# melzi.net
KiCad netlist of a schematic drawn in EAGLE
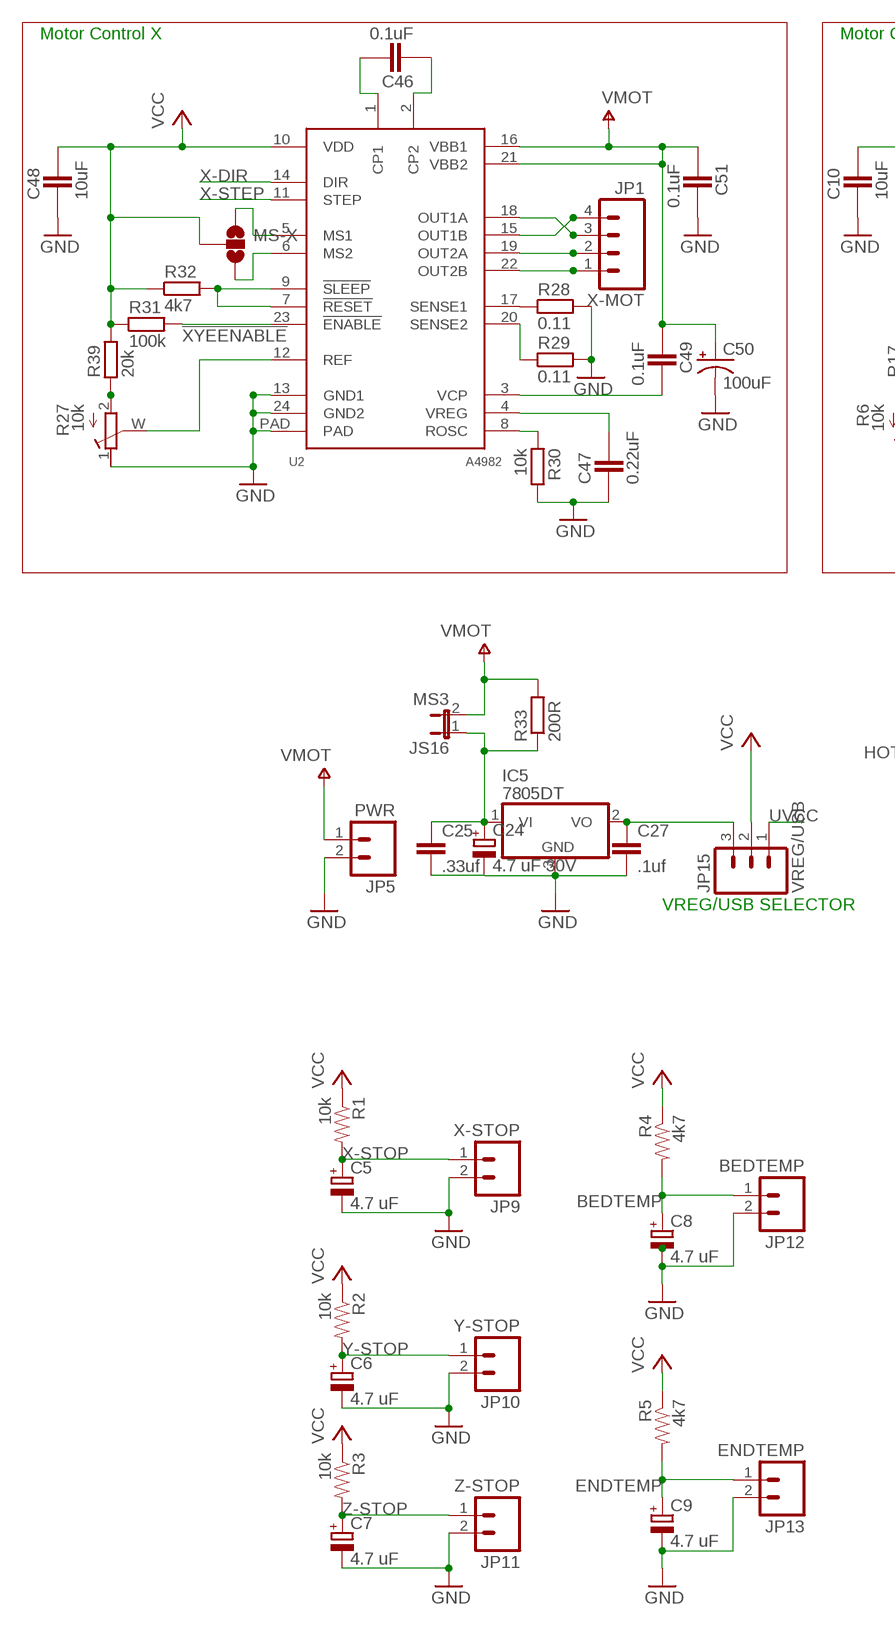
[diagram p0: schematic, sheet 1, part 1 of 2]
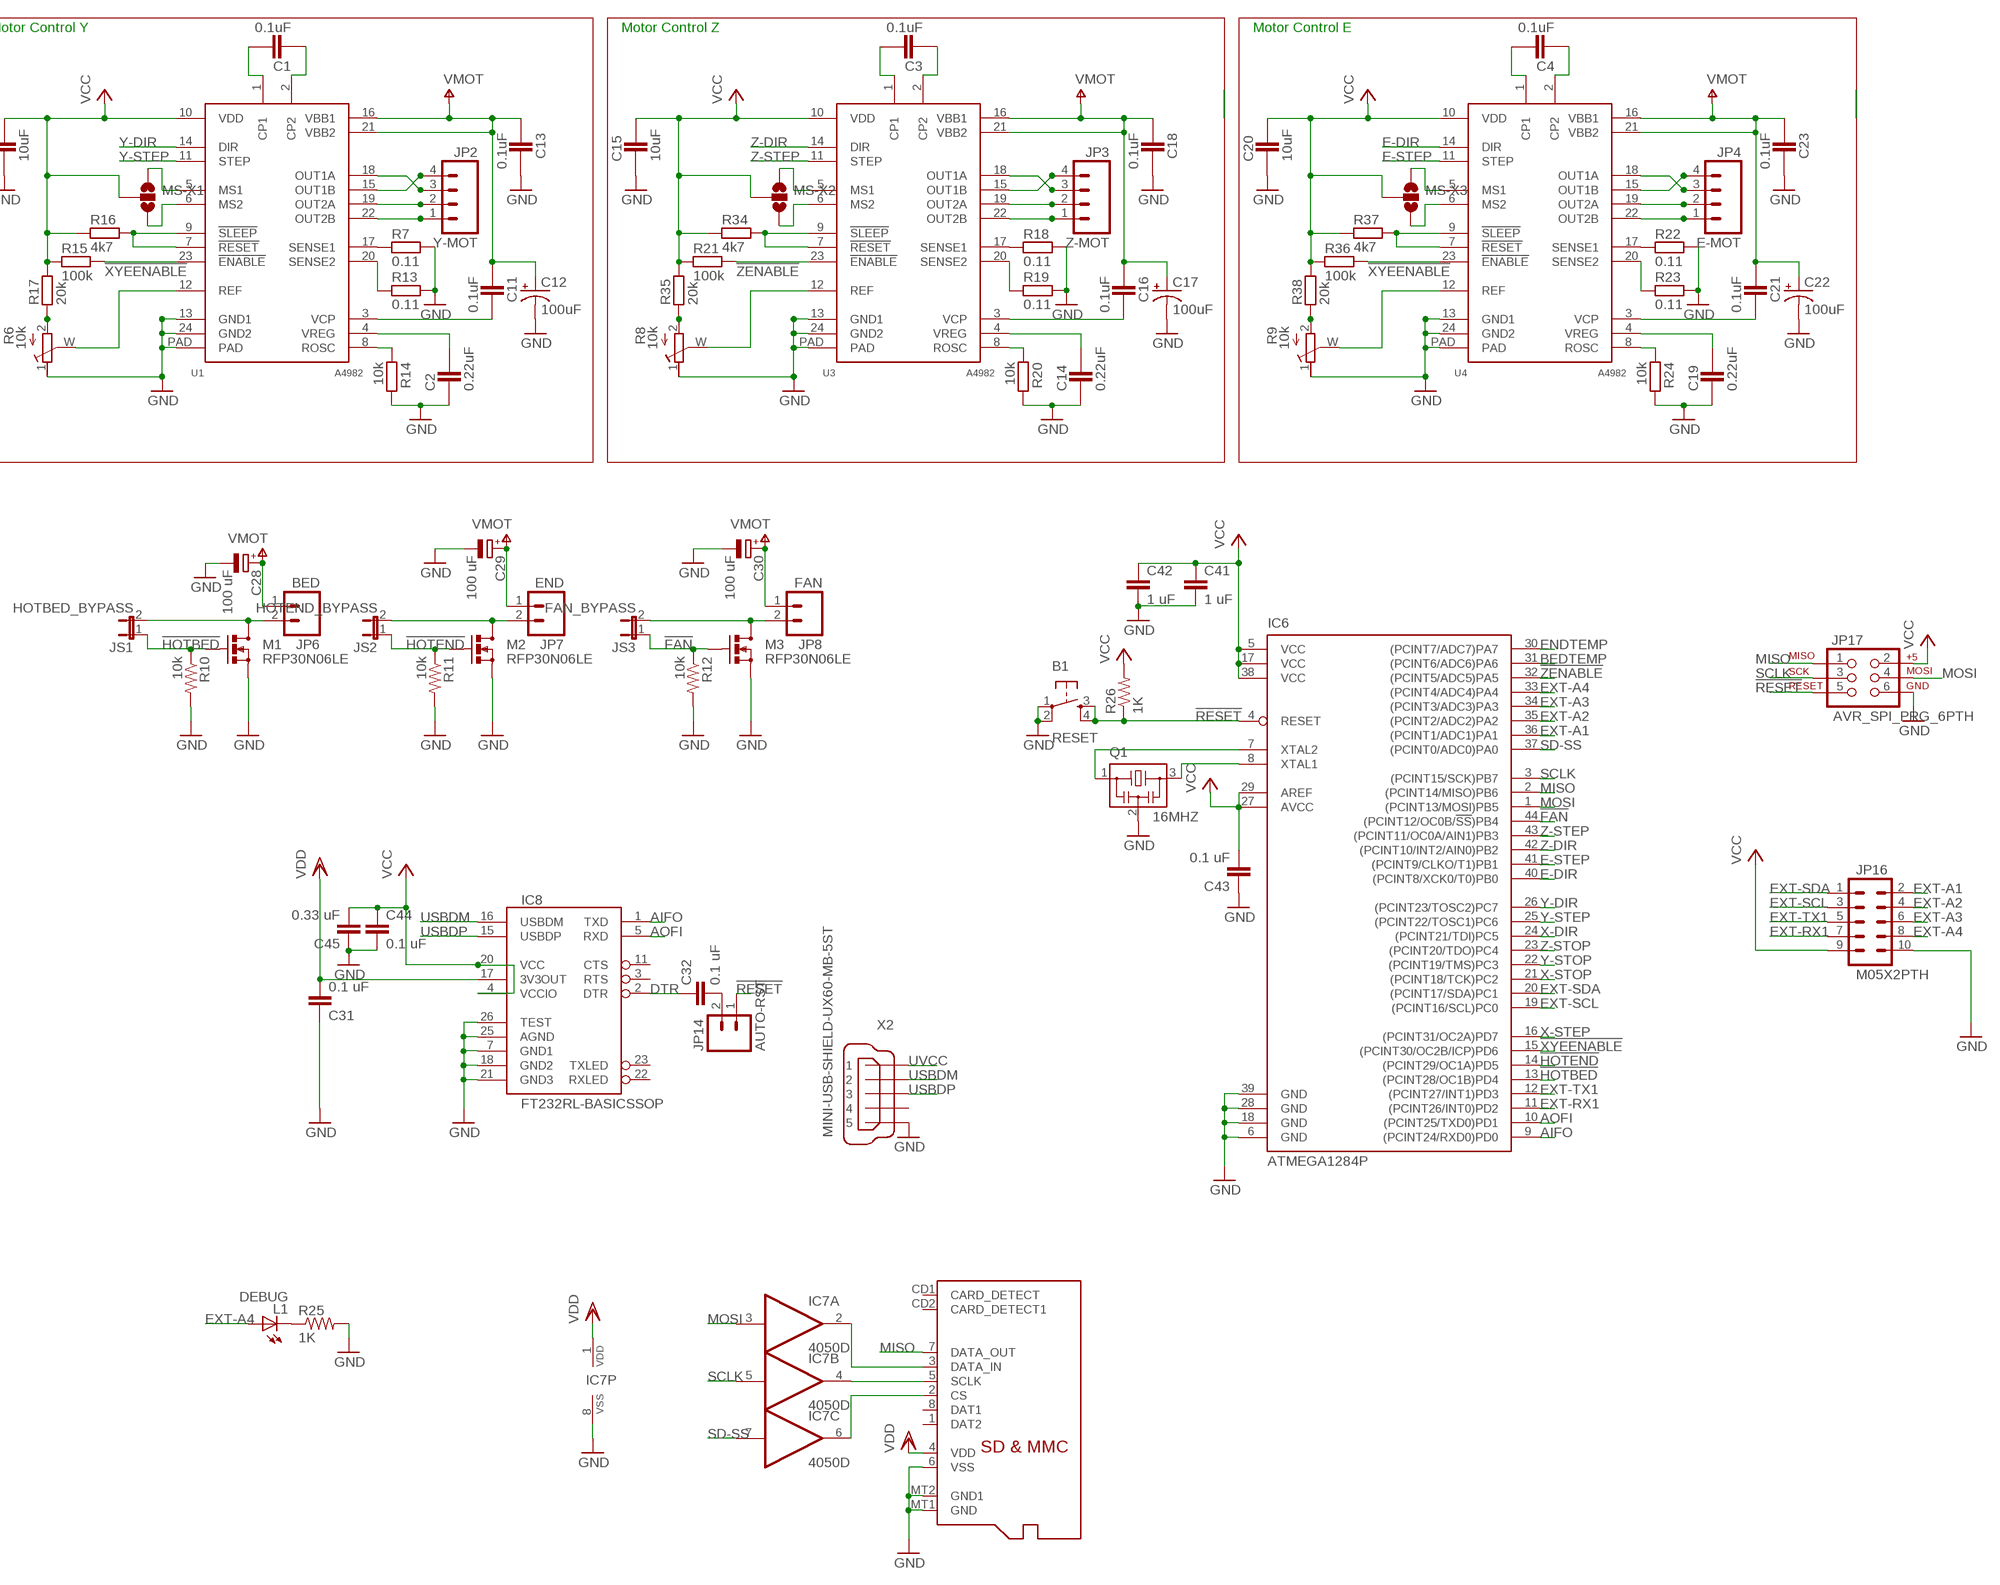
[diagram p1: schematic, sheet 1, part 2 of 2]

(export (version "E")
  (design (tool "Eeschema 10.0.6"))
  (components
    (comp (ref "B1")
      (value "RESET")
      (footprint "eagle-import:TACTILE_SWITCH_SMD")
      (libsource (lib "eagle-import") (part "TAC_SWITCHSMD"))
    )
    (comp (ref "C1")
      (value "0.1uF")
      (footprint "eagle-import:CAPC2012X145AN")
      (libsource (lib "eagle-import") (part "CAPACITOR_0805"))
    )
    (comp (ref "C2")
      (value "0.22uF")
      (footprint "eagle-import:CAPC2012X145AN")
      (libsource (lib "eagle-import") (part "CAPACITOR_0805"))
    )
    (comp (ref "C3")
      (value "0.1uF")
      (footprint "eagle-import:CAPC2012X145AN")
      (libsource (lib "eagle-import") (part "CAPACITOR_0805"))
    )
    (comp (ref "C4")
      (value "0.1uF")
      (footprint "eagle-import:CAPC2012X145AN")
      (libsource (lib "eagle-import") (part "CAPACITOR_0805"))
    )
    (comp (ref "C5")
      (value "4.7 uF")
      (footprint "eagle-import:SMC_C")
      (libsource (lib "eagle-import") (part "CPOL-EUSMCC"))
    )
    (comp (ref "C6")
      (value "4.7 uF")
      (footprint "eagle-import:SMC_C")
      (libsource (lib "eagle-import") (part "CPOL-EUSMCC"))
    )
    (comp (ref "C7")
      (value "4.7 uF")
      (footprint "eagle-import:SMC_C")
      (libsource (lib "eagle-import") (part "CPOL-EUSMCC"))
    )
    (comp (ref "C8")
      (value "4.7 uF")
      (footprint "eagle-import:SMC_C")
      (libsource (lib "eagle-import") (part "CPOL-EUSMCC"))
    )
    (comp (ref "C9")
      (value "4.7 uF")
      (footprint "eagle-import:SMC_C")
      (libsource (lib "eagle-import") (part "CPOL-EUSMCC"))
    )
    (comp (ref "C10")
      (value "10uF")
      (footprint "eagle-import:CAPC2012X145AN")
      (libsource (lib "eagle-import") (part "CAPACITOR_0805"))
    )
    (comp (ref "C11")
      (value "0.1uF")
      (footprint "eagle-import:CAPC2012X145AN")
      (libsource (lib "eagle-import") (part "CAPACITOR_0805"))
    )
    (comp (ref "C12")
      (value "100uF")
      (footprint "eagle-import:PANASONIC_D")
      (libsource (lib "eagle-import") (part "CPOL-USD"))
    )
    (comp (ref "C13")
      (value "0.1uF")
      (footprint "eagle-import:CAPC2012X145AN")
      (libsource (lib "eagle-import") (part "CAPACITOR_0805"))
    )
    (comp (ref "C14")
      (value "0.22uF")
      (footprint "eagle-import:CAPC2012X145AN")
      (libsource (lib "eagle-import") (part "CAPACITOR_0805"))
    )
    (comp (ref "C15")
      (value "10uF")
      (footprint "eagle-import:CAPC2012X145AN")
      (libsource (lib "eagle-import") (part "CAPACITOR_0805"))
    )
    (comp (ref "C16")
      (value "0.1uF")
      (footprint "eagle-import:CAPC2012X145AN")
      (libsource (lib "eagle-import") (part "CAPACITOR_0805"))
    )
    (comp (ref "C17")
      (value "100uF")
      (footprint "eagle-import:PANASONIC_D")
      (libsource (lib "eagle-import") (part "CPOL-USD"))
    )
    (comp (ref "C18")
      (value "0.1uF")
      (footprint "eagle-import:CAPC2012X145AN")
      (libsource (lib "eagle-import") (part "CAPACITOR_0805"))
    )
    (comp (ref "C19")
      (value "0.22uF")
      (footprint "eagle-import:CAPC2012X145AN")
      (libsource (lib "eagle-import") (part "CAPACITOR_0805"))
    )
    (comp (ref "C20")
      (value "10uF")
      (footprint "eagle-import:CAPC2012X145AN")
      (libsource (lib "eagle-import") (part "CAPACITOR_0805"))
    )
    (comp (ref "C21")
      (value "0.1uF")
      (footprint "eagle-import:CAPC2012X145AN")
      (libsource (lib "eagle-import") (part "CAPACITOR_0805"))
    )
    (comp (ref "C22")
      (value "100uF")
      (footprint "eagle-import:PANASONIC_D")
      (libsource (lib "eagle-import") (part "CPOL-USD"))
    )
    (comp (ref "C23")
      (value "0.1uF")
      (footprint "eagle-import:CAPC2012X145AN")
      (libsource (lib "eagle-import") (part "CAPACITOR_0805"))
    )
    (comp (ref "C24")
      (value "4.7 uF 30V")
      (footprint "eagle-import:SMC_C")
      (libsource (lib "eagle-import") (part "CPOL-EUSMCC"))
    )
    (comp (ref "C25")
      (value ".33uf")
      (footprint "eagle-import:0805")
      (libsource (lib "eagle-import") (part "CAP0805"))
    )
    (comp (ref "C27")
      (value ".1uf")
      (footprint "eagle-import:0805")
      (libsource (lib "eagle-import") (part "CAP0805"))
    )
    (comp (ref "C28")
      (value "100 uF")
      (footprint "eagle-import:UD-6,3X7,7_NICHICON")
      (libsource (lib "eagle-import") (part "CPOL-EUUD-6,3X7,7"))
    )
    (comp (ref "C29")
      (value "100 uF")
      (footprint "eagle-import:UD-6,3X7,7_NICHICON")
      (libsource (lib "eagle-import") (part "CPOL-EUUD-6,3X7,7"))
    )
    (comp (ref "C30")
      (value "100 uF")
      (footprint "eagle-import:UD-6,3X7,7_NICHICON")
      (libsource (lib "eagle-import") (part "CPOL-EUUD-6,3X7,7"))
    )
    (comp (ref "C31")
      (value "0.1 uF")
      (footprint "eagle-import:C1206")
      (libsource (lib "eagle-import") (part "C-EUC1206"))
    )
    (comp (ref "C32")
      (value "0.1 uF")
      (footprint "eagle-import:C1206")
      (libsource (lib "eagle-import") (part "C-EUC1206"))
    )
    (comp (ref "C41")
      (value "1 uF")
      (footprint "eagle-import:C1206")
      (libsource (lib "eagle-import") (part "C-EUC1206"))
    )
    (comp (ref "C42")
      (value "1 uF")
      (footprint "eagle-import:C1206")
      (libsource (lib "eagle-import") (part "C-EUC1206"))
    )
    (comp (ref "C43")
      (value "0.1 uF")
      (footprint "eagle-import:C1206")
      (libsource (lib "eagle-import") (part "C-EUC1206"))
    )
    (comp (ref "C44")
      (value "0.1 uF")
      (footprint "eagle-import:C1206")
      (libsource (lib "eagle-import") (part "C-EUC1206"))
    )
    (comp (ref "C45")
      (value "0.33 uF")
      (footprint "eagle-import:C1206")
      (libsource (lib "eagle-import") (part "C-EUC1206"))
    )
    (comp (ref "C46")
      (value "0.1uF")
      (footprint "eagle-import:CAPC2012X145AN")
      (libsource (lib "eagle-import") (part "CAPACITOR_0805"))
    )
    (comp (ref "C47")
      (value "0.22uF")
      (footprint "eagle-import:CAPC2012X145AN")
      (libsource (lib "eagle-import") (part "CAPACITOR_0805"))
    )
    (comp (ref "C48")
      (value "10uF")
      (footprint "eagle-import:CAPC2012X145AN")
      (libsource (lib "eagle-import") (part "CAPACITOR_0805"))
    )
    (comp (ref "C49")
      (value "0.1uF")
      (footprint "eagle-import:CAPC2012X145AN")
      (libsource (lib "eagle-import") (part "CAPACITOR_0805"))
    )
    (comp (ref "C50")
      (value "100uF")
      (footprint "eagle-import:PANASONIC_D")
      (libsource (lib "eagle-import") (part "CPOL-USD"))
    )
    (comp (ref "C51")
      (value "0.1uF")
      (footprint "eagle-import:CAPC2012X145AN")
      (libsource (lib "eagle-import") (part "CAPACITOR_0805"))
    )
    (comp (ref "IC5")
      (value "7805DT")
      (footprint "eagle-import:TO252")
      (libsource (lib "eagle-import") (part "78DT05"))
    )
    (comp (ref "IC6")
      (value "ATMEGA1284P")
      (footprint "eagle-import:TQFP44")
      (fields (field (name "MPN") "ATMEGA644PV-10AU"))
      (libsource (lib "eagle-import") (part "ATMEGA644A"))
    )
    (comp (ref "IC7")
      (value "4050D")
      (footprint "eagle-import:SO16")
      (libsource (lib "eagle-import") (part "4050D"))
    )
    (comp (ref "IC8")
      (value "FT232RL-BASICSSOP")
      (footprint "eagle-import:SSOP28DB")
      (libsource (lib "eagle-import") (part "FT232RL-BASICSSOP"))
    )
    (comp (ref "JP1")
      (value "X-MOT")
      (footprint "eagle-import:SCREWTERMINAL-3.5MM-4")
      (libsource (lib "eagle-import") (part "M04SCREW"))
    )
    (comp (ref "JP2")
      (value "Y-MOT")
      (footprint "eagle-import:SCREWTERMINAL-3.5MM-4")
      (libsource (lib "eagle-import") (part "M04SCREW"))
    )
    (comp (ref "JP3")
      (value "Z-MOT")
      (footprint "eagle-import:SCREWTERMINAL-3.5MM-4")
      (libsource (lib "eagle-import") (part "M04SCREW"))
    )
    (comp (ref "JP4")
      (value "E-MOT")
      (footprint "eagle-import:SCREWTERMINAL-3.5MM-4")
      (libsource (lib "eagle-import") (part "M04SCREW"))
    )
    (comp (ref "JP5")
      (value "PWR")
      (footprint "eagle-import:SCREWTERMINAL-5MM-2")
      (libsource (lib "eagle-import") (part "M025MM"))
    )
    (comp (ref "JP6")
      (value "BED")
      (footprint "eagle-import:SCREWTERMINAL-5MM-2")
      (libsource (lib "eagle-import") (part "M025MM"))
    )
    (comp (ref "JP7")
      (value "END")
      (footprint "eagle-import:SCREWTERMINAL-5MM-2")
      (libsource (lib "eagle-import") (part "M025MM"))
    )
    (comp (ref "JP8")
      (value "FAN")
      (footprint "eagle-import:SCREWTERMINAL-5MM-2")
      (libsource (lib "eagle-import") (part "M025MM"))
    )
    (comp (ref "JP9")
      (value "X-STOP")
      (footprint "eagle-import:SCREWTERMINAL-3.5MM-2")
      (libsource (lib "eagle-import") (part "M023.5MM"))
    )
    (comp (ref "JP10")
      (value "Y-STOP")
      (footprint "eagle-import:SCREWTERMINAL-3.5MM-2")
      (libsource (lib "eagle-import") (part "M023.5MM"))
    )
    (comp (ref "JP11")
      (value "Z-STOP")
      (footprint "eagle-import:SCREWTERMINAL-3.5MM-2")
      (libsource (lib "eagle-import") (part "M023.5MM"))
    )
    (comp (ref "JP12")
      (value "BEDTEMP")
      (footprint "eagle-import:SCREWTERMINAL-3.5MM-2")
      (libsource (lib "eagle-import") (part "M023.5MM"))
    )
    (comp (ref "JP13")
      (value "ENDTEMP")
      (footprint "eagle-import:SCREWTERMINAL-3.5MM-2")
      (libsource (lib "eagle-import") (part "M023.5MM"))
    )
    (comp (ref "JP14")
      (value "AUTO-RST")
      (footprint "eagle-import:1X02")
      (libsource (lib "eagle-import") (part "M02PTH"))
    )
    (comp (ref "JP15")
      (value "VREG/USB")
      (footprint "eagle-import:1X03")
      (libsource (lib "eagle-import") (part "M03PTH"))
    )
    (comp (ref "JP16")
      (value "M05X2PTH")
      (footprint "eagle-import:AVR_ICSP")
      (libsource (lib "eagle-import") (part "M05X2PTH"))
    )
    (comp (ref "JP17")
      (value "AVR_SPI_PRG_6PTH")
      (footprint "eagle-import:2X3")
      (libsource (lib "eagle-import") (part "AVR_SPI_PRG_6PTH"))
    )
    (comp (ref "JS1")
      (value "HOTBED_BYPASS")
      (footprint "eagle-import:SJ_2S-NO")
      (libsource (lib "eagle-import") (part "JUMPER-2SMD-NO"))
    )
    (comp (ref "JS2")
      (value "HOTEND_BYPASS")
      (footprint "eagle-import:SJ_2S-NO")
      (libsource (lib "eagle-import") (part "JUMPER-2SMD-NO"))
    )
    (comp (ref "JS3")
      (value "FAN_BYPASS")
      (footprint "eagle-import:SJ_2S-NO")
      (libsource (lib "eagle-import") (part "JUMPER-2SMD-NO"))
    )
    (comp (ref "JS16")
      (value "MS3")
      (footprint "eagle-import:SJ_2S")
      (libsource (lib "eagle-import") (part "JUMPER-2SMD-NC"))
    )
    (comp (ref "L1")
      (value "DEBUG")
      (footprint "eagle-import:LED-1206")
      (libsource (lib "eagle-import") (part "LED1206"))
    )
    (comp (ref "M1")
      (value "RFP30N06LE")
      (footprint "eagle-import:DPAK")
      (libsource (lib "eagle-import") (part "MOSFET-NCHANNELFDD8580"))
    )
    (comp (ref "M2")
      (value "RFP30N06LE")
      (footprint "eagle-import:DPAK")
      (libsource (lib "eagle-import") (part "MOSFET-NCHANNELFDD8580"))
    )
    (comp (ref "M3")
      (value "RFP30N06LE")
      (footprint "eagle-import:DPAK")
      (libsource (lib "eagle-import") (part "MOSFET-NCHANNELFDD8580"))
    )
    (comp (ref "MS-X")
      (value "SOLDERJUMPER_2WAYCONNECTED")
      (footprint "eagle-import:SJ_3_CONNECTED")
      (libsource (lib "eagle-import") (part "SOLDERJUMPER_2WAYCONNECTED"))
    )
    (comp (ref "MS-X1")
      (value "SOLDERJUMPER_2WAYCONNECTED")
      (footprint "eagle-import:SJ_3_CONNECTED")
      (libsource (lib "eagle-import") (part "SOLDERJUMPER_2WAYCONNECTED"))
    )
    (comp (ref "MS-X2")
      (value "SOLDERJUMPER_2WAYCONNECTED")
      (footprint "eagle-import:SJ_3_CONNECTED")
      (libsource (lib "eagle-import") (part "SOLDERJUMPER_2WAYCONNECTED"))
    )
    (comp (ref "MS-X3")
      (value "SOLDERJUMPER_2WAYCONNECTED")
      (footprint "eagle-import:SJ_3_CONNECTED")
      (libsource (lib "eagle-import") (part "SOLDERJUMPER_2WAYCONNECTED"))
    )
    (comp (ref "Q1")
      (value "16MHZ")
      (footprint "eagle-import:CSTCR6M")
      (fields (field (name "MPN") "CSTCR6M00G53-R0"))
      (libsource (lib "eagle-import") (part "CSTCR6M00G53Z"))
    )
    (comp (ref "R1")
      (value "10k")
      (footprint "eagle-import:1206")
      (libsource (lib "eagle-import") (part "RESISTOR1206"))
    )
    (comp (ref "R2")
      (value "10k")
      (footprint "eagle-import:1206")
      (libsource (lib "eagle-import") (part "RESISTOR1206"))
    )
    (comp (ref "R3")
      (value "10k")
      (footprint "eagle-import:1206")
      (libsource (lib "eagle-import") (part "RESISTOR1206"))
    )
    (comp (ref "R4")
      (value "4k7")
      (footprint "eagle-import:1206")
      (libsource (lib "eagle-import") (part "RESISTOR1206"))
    )
    (comp (ref "R5")
      (value "4k7")
      (footprint "eagle-import:1206")
      (libsource (lib "eagle-import") (part "RESISTOR1206"))
    )
    (comp (ref "R6")
      (value "10k")
      (footprint "eagle-import:RTRIM-ST4ETB")
      (libsource (lib "eagle-import") (part "RTRIM-ST-4EA"))
    )
    (comp (ref "R7")
      (value "0.11")
      (footprint "eagle-import:RESC2012X70N")
      (libsource (lib "eagle-import") (part "RESISTOR_0805"))
    )
    (comp (ref "R8")
      (value "10k")
      (footprint "eagle-import:RTRIM-ST4ETB")
      (libsource (lib "eagle-import") (part "RTRIM-ST-4EA"))
    )
    (comp (ref "R9")
      (value "10k")
      (footprint "eagle-import:RTRIM-ST4ETB")
      (libsource (lib "eagle-import") (part "RTRIM-ST-4EA"))
    )
    (comp (ref "R10")
      (value "10k")
      (footprint "eagle-import:1206")
      (libsource (lib "eagle-import") (part "RESISTOR1206"))
    )
    (comp (ref "R11")
      (value "10k")
      (footprint "eagle-import:1206")
      (libsource (lib "eagle-import") (part "RESISTOR1206"))
    )
    (comp (ref "R12")
      (value "10k")
      (footprint "eagle-import:1206")
      (libsource (lib "eagle-import") (part "RESISTOR1206"))
    )
    (comp (ref "R13")
      (value "0.11")
      (footprint "eagle-import:RESC2012X70N")
      (libsource (lib "eagle-import") (part "RESISTOR_0805"))
    )
    (comp (ref "R14")
      (value "10k")
      (footprint "eagle-import:RESC2012X70N")
      (libsource (lib "eagle-import") (part "RESISTOR_0805"))
    )
    (comp (ref "R15")
      (value "100k")
      (footprint "eagle-import:RESC2012X70N")
      (libsource (lib "eagle-import") (part "RESISTOR_0805"))
    )
    (comp (ref "R16")
      (value "4k7")
      (footprint "eagle-import:RESC2012X70N")
      (libsource (lib "eagle-import") (part "RESISTOR_0805"))
    )
    (comp (ref "R17")
      (value "20k")
      (footprint "eagle-import:RESC2012X70N")
      (libsource (lib "eagle-import") (part "RESISTOR_0805"))
    )
    (comp (ref "R18")
      (value "0.11")
      (footprint "eagle-import:RESC2012X70N")
      (libsource (lib "eagle-import") (part "RESISTOR_0805"))
    )
    (comp (ref "R19")
      (value "0.11")
      (footprint "eagle-import:RESC2012X70N")
      (libsource (lib "eagle-import") (part "RESISTOR_0805"))
    )
    (comp (ref "R20")
      (value "10k")
      (footprint "eagle-import:RESC2012X70N")
      (libsource (lib "eagle-import") (part "RESISTOR_0805"))
    )
    (comp (ref "R21")
      (value "100k")
      (footprint "eagle-import:RESC2012X70N")
      (libsource (lib "eagle-import") (part "RESISTOR_0805"))
    )
    (comp (ref "R22")
      (value "0.11")
      (footprint "eagle-import:RESC2012X70N")
      (libsource (lib "eagle-import") (part "RESISTOR_0805"))
    )
    (comp (ref "R23")
      (value "0.11")
      (footprint "eagle-import:RESC2012X70N")
      (libsource (lib "eagle-import") (part "RESISTOR_0805"))
    )
    (comp (ref "R24")
      (value "10k")
      (footprint "eagle-import:RESC2012X70N")
      (libsource (lib "eagle-import") (part "RESISTOR_0805"))
    )
    (comp (ref "R25")
      (value "1K")
      (footprint "eagle-import:1206")
      (libsource (lib "eagle-import") (part "RESISTOR1206"))
    )
    (comp (ref "R26")
      (value "1K")
      (footprint "eagle-import:1206")
      (libsource (lib "eagle-import") (part "RESISTOR1206"))
    )
    (comp (ref "R27")
      (value "10k")
      (footprint "eagle-import:RTRIM-ST4ETB")
      (libsource (lib "eagle-import") (part "RTRIM-ST-4EA"))
    )
    (comp (ref "R28")
      (value "0.11")
      (footprint "eagle-import:RESC2012X70N")
      (libsource (lib "eagle-import") (part "RESISTOR_0805"))
    )
    (comp (ref "R29")
      (value "0.11")
      (footprint "eagle-import:RESC2012X70N")
      (libsource (lib "eagle-import") (part "RESISTOR_0805"))
    )
    (comp (ref "R30")
      (value "10k")
      (footprint "eagle-import:RESC2012X70N")
      (libsource (lib "eagle-import") (part "RESISTOR_0805"))
    )
    (comp (ref "R31")
      (value "100k")
      (footprint "eagle-import:RESC2012X70N")
      (libsource (lib "eagle-import") (part "RESISTOR_0805"))
    )
    (comp (ref "R32")
      (value "4k7")
      (footprint "eagle-import:RESC2012X70N")
      (libsource (lib "eagle-import") (part "RESISTOR_0805"))
    )
    (comp (ref "R33")
      (value "200R")
      (footprint "eagle-import:0309V")
      (libsource (lib "eagle-import") (part "R-EU_0309/V"))
    )
    (comp (ref "R34")
      (value "4k7")
      (footprint "eagle-import:RESC2012X70N")
      (libsource (lib "eagle-import") (part "RESISTOR_0805"))
    )
    (comp (ref "R35")
      (value "20k")
      (footprint "eagle-import:RESC2012X70N")
      (libsource (lib "eagle-import") (part "RESISTOR_0805"))
    )
    (comp (ref "R36")
      (value "100k")
      (footprint "eagle-import:RESC2012X70N")
      (libsource (lib "eagle-import") (part "RESISTOR_0805"))
    )
    (comp (ref "R37")
      (value "4k7")
      (footprint "eagle-import:RESC2012X70N")
      (libsource (lib "eagle-import") (part "RESISTOR_0805"))
    )
    (comp (ref "R38")
      (value "20k")
      (footprint "eagle-import:RESC2012X70N")
      (libsource (lib "eagle-import") (part "RESISTOR_0805"))
    )
    (comp (ref "R39")
      (value "20k")
      (footprint "eagle-import:RESC2012X70N")
      (libsource (lib "eagle-import") (part "RESISTOR_0805"))
    )
    (comp (ref "U1")
      (value "A4982")
      (footprint "eagle-import:TSSOP-24")
      (libsource (lib "eagle-import") (part "A4982"))
    )
    (comp (ref "U2")
      (value "A4982")
      (footprint "eagle-import:TSSOP-24")
      (libsource (lib "eagle-import") (part "A4982"))
    )
    (comp (ref "U3")
      (value "A4982")
      (footprint "eagle-import:TSSOP-24")
      (libsource (lib "eagle-import") (part "A4982"))
    )
    (comp (ref "U4")
      (value "A4982")
      (footprint "eagle-import:TSSOP-24")
      (libsource (lib "eagle-import") (part "A4982"))
    )
    (comp (ref "X1")
      (value "MICROSD")
      (footprint "eagle-import:MICROSD")
      (libsource (lib "eagle-import") (part "MICROSD"))
    )
    (comp (ref "X2")
      (value "MINI-USB-SHIELD-UX60-MB-5ST")
      (footprint "eagle-import:UX60-MB-5ST")
      (libsource (lib "eagle-import") (part "MINI-USB-SHIELD-UX60-MB-5ST"))
    )
  )
  (nets
    (net (code "1") (name "/AIFO") (class "Default")
      (node (ref "IC6") (pin "9") (pinfunction "(PCINT24/RXD0)PD0_9") (pintype "bidirectional"))
      (node (ref "IC8") (pin "1") (pinfunction "TXD_1") (pintype "output"))
    )
    (net (code "2") (name "/AOFI") (class "Default")
      (node (ref "IC6") (pin "10") (pinfunction "(PCINT25/TXD0)PD1_10") (pintype "bidirectional"))
      (node (ref "IC8") (pin "5") (pinfunction "RXD_5") (pintype "input"))
    )
    (net (code "3") (name "/BEDTEMP") (class "Default")
      (node (ref "C8") (pin "+") (pinfunction "+_+") (pintype "passive"))
      (node (ref "IC6") (pin "31") (pinfunction "(PCINT6/ADC6)PA6_31") (pintype "bidirectional"))
      (node (ref "JP12") (pin "1") (pinfunction "1_1") (pintype "passive"))
      (node (ref "R4") (pin "2") (pinfunction "2_2") (pintype "passive"))
    )
    (net (code "4") (name "/DTR") (class "Default")
      (node (ref "C32") (pin "1") (pinfunction "1_1") (pintype "passive"))
      (node (ref "IC8") (pin "2") (pinfunction "DTR_2") (pintype "bidirectional"))
    )
    (net (code "5") (name "/E-DIR") (class "Default")
      (node (ref "IC6") (pin "40") (pinfunction "(PCINT8/XCK0/T0)PB0_40") (pintype "bidirectional"))
      (node (ref "U4") (pin "14") (pinfunction "DIR_14") (pintype "input"))
    )
    (net (code "6") (name "/E-STEP") (class "Default")
      (node (ref "IC6") (pin "41") (pinfunction "(PCINT9/CLKO/T1)PB1_41") (pintype "bidirectional"))
      (node (ref "U4") (pin "11") (pinfunction "STEP_11") (pintype "input"))
    )
    (net (code "7") (name "/ENDTEMP") (class "Default")
      (node (ref "C9") (pin "+") (pinfunction "+_+") (pintype "passive"))
      (node (ref "IC6") (pin "30") (pinfunction "(PCINT7/ADC7)PA7_30") (pintype "bidirectional"))
      (node (ref "JP13") (pin "1") (pinfunction "1_1") (pintype "passive"))
      (node (ref "R5") (pin "2") (pinfunction "2_2") (pintype "passive"))
    )
    (net (code "8") (name "/EXT-A1") (class "Default")
      (node (ref "IC6") (pin "36") (pinfunction "(PCINT1/ADC1)PA1_36") (pintype "bidirectional"))
      (node (ref "JP16") (pin "2") (pinfunction "2_2") (pintype "passive"))
    )
    (net (code "9") (name "/EXT-A2") (class "Default")
      (node (ref "IC6") (pin "35") (pinfunction "(PCINT2/ADC2)PA2_35") (pintype "bidirectional"))
      (node (ref "JP16") (pin "4") (pinfunction "4_4") (pintype "passive"))
    )
    (net (code "10") (name "/EXT-A3") (class "Default")
      (node (ref "IC6") (pin "34") (pinfunction "(PCINT3/ADC3)PA3_34") (pintype "bidirectional"))
      (node (ref "JP16") (pin "6") (pinfunction "6_6") (pintype "passive"))
    )
    (net (code "11") (name "/EXT-A4") (class "Default")
      (node (ref "IC6") (pin "33") (pinfunction "(PCINT4/ADC4)PA4_33") (pintype "bidirectional"))
      (node (ref "JP16") (pin "8") (pinfunction "8_8") (pintype "passive"))
      (node (ref "L1") (pin "A") (pinfunction "A_A") (pintype "passive"))
    )
    (net (code "12") (name "/EXT-RX1") (class "Default")
      (node (ref "IC6") (pin "11") (pinfunction "(PCINT26/INT0)PD2_11") (pintype "bidirectional"))
      (node (ref "JP16") (pin "7") (pinfunction "7_7") (pintype "passive"))
    )
    (net (code "13") (name "/EXT-SCL") (class "Default")
      (node (ref "IC6") (pin "19") (pinfunction "(PCINT16/SCL)PC0_19") (pintype "output"))
      (node (ref "JP16") (pin "3") (pinfunction "3_3") (pintype "passive"))
    )
    (net (code "14") (name "/EXT-SDA") (class "Default")
      (node (ref "IC6") (pin "20") (pinfunction "(PCINT17/SDA)PC1_20") (pintype "output"))
      (node (ref "JP16") (pin "1") (pinfunction "1_1") (pintype "passive"))
    )
    (net (code "15") (name "/EXT-TX1") (class "Default")
      (node (ref "IC6") (pin "12") (pinfunction "(PCINT27/INT1)PD3_12") (pintype "bidirectional"))
      (node (ref "JP16") (pin "5") (pinfunction "5_5") (pintype "passive"))
    )
    (net (code "16") (name "/MISO") (class "Default")
      (node (ref "IC6") (pin "2") (pinfunction "(PCINT14/MISO)PB6_2") (pintype "bidirectional"))
      (node (ref "JP17") (pin "1") (pinfunction "1_1") (pintype "passive"))
      (node (ref "X1") (pin "7") (pinfunction "DATA_OUT_7") (pintype "output"))
    )
    (net (code "17") (name "/MOSI") (class "Default")
      (node (ref "IC6") (pin "1") (pinfunction "(PCINT13/MOSI)PB5_1") (pintype "bidirectional"))
      (node (ref "IC7") (pin "3") (pinfunction "I_3") (pintype "input"))
      (node (ref "JP17") (pin "4") (pinfunction "4_4") (pintype "passive"))
    )
    (net (code "18") (name "/SCLK") (class "Default")
      (node (ref "IC6") (pin "3") (pinfunction "(PCINT15/SCK)PB7_3") (pintype "bidirectional"))
      (node (ref "IC7") (pin "5") (pinfunction "I_5") (pintype "input"))
      (node (ref "JP17") (pin "3") (pinfunction "3_3") (pintype "passive"))
    )
    (net (code "19") (name "/SD-SS") (class "Default")
      (node (ref "IC6") (pin "37") (pinfunction "(PCINT0/ADC0)PA0_37") (pintype "bidirectional"))
      (node (ref "IC7") (pin "7") (pinfunction "I_7") (pintype "input"))
    )
    (net (code "20") (name "/USBDM") (class "Default")
      (node (ref "IC8") (pin "16") (pinfunction "USBDM_16") (pintype "bidirectional"))
      (node (ref "X2") (pin "2") (pinfunction "2_2") (pintype "input"))
    )
    (net (code "21") (name "/USBDP") (class "Default")
      (node (ref "IC8") (pin "15") (pinfunction "USBDP_15") (pintype "bidirectional"))
      (node (ref "X2") (pin "3") (pinfunction "3_3") (pintype "input"))
    )
    (net (code "22") (name "/UVCC") (class "Default")
      (node (ref "JP15") (pin "1") (pinfunction "1_1") (pintype "passive"))
      (node (ref "X2") (pin "1") (pinfunction "1_1") (pintype "input"))
    )
    (net (code "23") (name "/X-DIR") (class "Default")
      (node (ref "IC6") (pin "24") (pinfunction "(PCINT21/TDI)PC5_24") (pintype "output"))
      (node (ref "U2") (pin "14") (pinfunction "DIR_14") (pintype "input"))
    )
    (net (code "24") (name "/X-STEP") (class "Default")
      (node (ref "IC6") (pin "16") (pinfunction "(PCINT31/OC2A)PD7_16") (pintype "bidirectional"))
      (node (ref "U2") (pin "11") (pinfunction "STEP_11") (pintype "input"))
    )
    (net (code "25") (name "/X-STOP") (class "Default")
      (node (ref "C5") (pin "+") (pinfunction "+_+") (pintype "passive"))
      (node (ref "IC6") (pin "21") (pinfunction "(PCINT18/TCK)PC2_21") (pintype "output"))
      (node (ref "JP9") (pin "1") (pinfunction "1_1") (pintype "passive"))
      (node (ref "R1") (pin "2") (pinfunction "2_2") (pintype "passive"))
    )
    (net (code "26") (name "/Y-DIR") (class "Default")
      (node (ref "IC6") (pin "26") (pinfunction "(PCINT23/TOSC2)PC7_26") (pintype "output"))
      (node (ref "U1") (pin "14") (pinfunction "DIR_14") (pintype "input"))
    )
    (net (code "27") (name "/Y-STEP") (class "Default")
      (node (ref "IC6") (pin "25") (pinfunction "(PCINT22/TOSC1)PC6_25") (pintype "output"))
      (node (ref "U1") (pin "11") (pinfunction "STEP_11") (pintype "input"))
    )
    (net (code "28") (name "/Y-STOP") (class "Default")
      (node (ref "C6") (pin "+") (pinfunction "+_+") (pintype "passive"))
      (node (ref "IC6") (pin "22") (pinfunction "(PCINT19/TMS)PC3_22") (pintype "output"))
      (node (ref "JP10") (pin "1") (pinfunction "1_1") (pintype "passive"))
      (node (ref "R2") (pin "2") (pinfunction "2_2") (pintype "passive"))
    )
    (net (code "29") (name "/Z-DIR") (class "Default")
      (node (ref "IC6") (pin "42") (pinfunction "(PCINT10/INT2/AIN0)PB2_42") (pintype "bidirectional"))
      (node (ref "U3") (pin "14") (pinfunction "DIR_14") (pintype "input"))
    )
    (net (code "30") (name "/Z-STEP") (class "Default")
      (node (ref "IC6") (pin "43") (pinfunction "(PCINT11/OC0A/AIN1)PB3_43") (pintype "bidirectional"))
      (node (ref "U3") (pin "11") (pinfunction "STEP_11") (pintype "input"))
    )
    (net (code "31") (name "/Z-STOP") (class "Default")
      (node (ref "C7") (pin "+") (pinfunction "+_+") (pintype "passive"))
      (node (ref "IC6") (pin "23") (pinfunction "(PCINT20/TDO)PC4_23") (pintype "output"))
      (node (ref "JP11") (pin "1") (pinfunction "1_1") (pintype "passive"))
      (node (ref "R3") (pin "2") (pinfunction "2_2") (pintype "passive"))
    )
    (net (code "32") (name "/~{FAN}") (class "Default")
      (node (ref "IC6") (pin "44") (pinfunction "(PCINT12/OC0B/~{SS})PB4_44") (pintype "bidirectional"))
      (node (ref "JS3") (pin "1") (pinfunction "1_1") (pintype "passive"))
      (node (ref "M3") (pin "1") (pinfunction "G_1") (pintype "passive"))
      (node (ref "R12") (pin "1") (pinfunction "1_1") (pintype "passive"))
    )
    (net (code "33") (name "/~{HOTBED}") (class "Default")
      (node (ref "IC6") (pin "13") (pinfunction "(PCINT28/OC1B)PD4_13") (pintype "bidirectional"))
      (node (ref "JS1") (pin "1") (pinfunction "1_1") (pintype "passive"))
      (node (ref "M1") (pin "1") (pinfunction "G_1") (pintype "passive"))
      (node (ref "R10") (pin "1") (pinfunction "1_1") (pintype "passive"))
    )
    (net (code "34") (name "/~{HOTEND}") (class "Default")
      (node (ref "IC6") (pin "14") (pinfunction "(PCINT29/OC1A)PD5_14") (pintype "bidirectional"))
      (node (ref "JS2") (pin "1") (pinfunction "1_1") (pintype "passive"))
      (node (ref "M2") (pin "1") (pinfunction "G_1") (pintype "passive"))
      (node (ref "R11") (pin "1") (pinfunction "1_1") (pintype "passive"))
    )
    (net (code "35") (name "/~{RESET}") (class "Default")
      (node (ref "B1") (pin "3") (pinfunction "3_3") (pintype "passive"))
      (node (ref "B1") (pin "4") (pinfunction "4_4") (pintype "passive"))
      (node (ref "IC6") (pin "4") (pinfunction "RESET_4") (pintype "input"))
      (node (ref "JP14") (pin "1") (pinfunction "1_1") (pintype "passive"))
      (node (ref "JP17") (pin "5") (pinfunction "5_5") (pintype "passive"))
      (node (ref "R26") (pin "1") (pinfunction "1_1") (pintype "passive"))
    )
    (net (code "36") (name "/~{XYEENABLE}") (class "Default")
      (node (ref "IC6") (pin "15") (pinfunction "(PCINT30/OC2B/ICP)PD6_15") (pintype "bidirectional"))
      (node (ref "R15") (pin "2") (pinfunction "2_2") (pintype "passive"))
      (node (ref "R31") (pin "2") (pinfunction "2_2") (pintype "passive"))
      (node (ref "R36") (pin "2") (pinfunction "2_2") (pintype "passive"))
      (node (ref "U1") (pin "23") (pinfunction "~{ENABLE}_23") (pintype "input"))
      (node (ref "U2") (pin "23") (pinfunction "~{ENABLE}_23") (pintype "input"))
      (node (ref "U4") (pin "23") (pinfunction "~{ENABLE}_23") (pintype "input"))
    )
    (net (code "37") (name "/~{ZENABLE}") (class "Default")
      (node (ref "IC6") (pin "32") (pinfunction "(PCINT5/ADC5)PA5_32") (pintype "bidirectional"))
      (node (ref "R21") (pin "2") (pinfunction "2_2") (pintype "passive"))
      (node (ref "U3") (pin "23") (pinfunction "~{ENABLE}_23") (pintype "input"))
    )
    (net (code "38") (name "GND") (class "Default")
      (node (ref "B1") (pin "1") (pinfunction "1_1") (pintype "passive"))
      (node (ref "B1") (pin "2") (pinfunction "2_2") (pintype "passive"))
      (node (ref "C10") (pin "1") (pinfunction "1_1") (pintype "passive"))
      (node (ref "C12") (pin "-") (pinfunction "-_-") (pintype "passive"))
      (node (ref "C13") (pin "2") (pinfunction "2_2") (pintype "passive"))
      (node (ref "C14") (pin "1") (pinfunction "1_1") (pintype "passive"))
      (node (ref "C15") (pin "1") (pinfunction "1_1") (pintype "passive"))
      (node (ref "C17") (pin "-") (pinfunction "-_-") (pintype "passive"))
      (node (ref "C18") (pin "2") (pinfunction "2_2") (pintype "passive"))
      (node (ref "C19") (pin "1") (pinfunction "1_1") (pintype "passive"))
      (node (ref "C2") (pin "1") (pinfunction "1_1") (pintype "passive"))
      (node (ref "C20") (pin "1") (pinfunction "1_1") (pintype "passive"))
      (node (ref "C22") (pin "-") (pinfunction "-_-") (pintype "passive"))
      (node (ref "C23") (pin "2") (pinfunction "2_2") (pintype "passive"))
      (node (ref "C24") (pin "-") (pinfunction "-_-") (pintype "passive"))
      (node (ref "C25") (pin "2") (pinfunction "2_2") (pintype "passive"))
      (node (ref "C27") (pin "2") (pinfunction "2_2") (pintype "passive"))
      (node (ref "C28") (pin "-") (pinfunction "-_-") (pintype "passive"))
      (node (ref "C29") (pin "-") (pinfunction "-_-") (pintype "passive"))
      (node (ref "C30") (pin "-") (pinfunction "-_-") (pintype "passive"))
      (node (ref "C31") (pin "1") (pinfunction "1_1") (pintype "passive"))
      (node (ref "C41") (pin "2") (pinfunction "2_2") (pintype "passive"))
      (node (ref "C42") (pin "2") (pinfunction "2_2") (pintype "passive"))
      (node (ref "C43") (pin "1") (pinfunction "1_1") (pintype "passive"))
      (node (ref "C44") (pin "2") (pinfunction "2_2") (pintype "passive"))
      (node (ref "C45") (pin "1") (pinfunction "1_1") (pintype "passive"))
      (node (ref "C47") (pin "1") (pinfunction "1_1") (pintype "passive"))
      (node (ref "C48") (pin "1") (pinfunction "1_1") (pintype "passive"))
      (node (ref "C5") (pin "-") (pinfunction "-_-") (pintype "passive"))
      (node (ref "C50") (pin "-") (pinfunction "-_-") (pintype "passive"))
      (node (ref "C51") (pin "2") (pinfunction "2_2") (pintype "passive"))
      (node (ref "C6") (pin "-") (pinfunction "-_-") (pintype "passive"))
      (node (ref "C7") (pin "-") (pinfunction "-_-") (pintype "passive"))
      (node (ref "C8") (pin "-") (pinfunction "-_-") (pintype "passive"))
      (node (ref "C9") (pin "-") (pinfunction "-_-") (pintype "passive"))
      (node (ref "IC5") (pin "3") (pinfunction "GND_3") (pintype "passive"))
      (node (ref "IC6") (pin "18") (pinfunction "GND_18") (pintype "power_in"))
      (node (ref "IC6") (pin "28") (pinfunction "GND_28") (pintype "power_in"))
      (node (ref "IC6") (pin "39") (pinfunction "GND_39") (pintype "power_in"))
      (node (ref "IC6") (pin "6") (pinfunction "GND_6") (pintype "power_in"))
      (node (ref "IC7") (pin "8") (pinfunction "VSS_8") (pintype "power_in"))
      (node (ref "IC8") (pin "18") (pinfunction "GND2_18") (pintype "power_in"))
      (node (ref "IC8") (pin "21") (pinfunction "GND3_21") (pintype "power_in"))
      (node (ref "IC8") (pin "25") (pinfunction "AGND_25") (pintype "power_in"))
      (node (ref "IC8") (pin "26") (pinfunction "TEST_26") (pintype "input"))
      (node (ref "IC8") (pin "7") (pinfunction "GND1_7") (pintype "power_in"))
      (node (ref "JP10") (pin "2") (pinfunction "2_2") (pintype "passive"))
      (node (ref "JP11") (pin "2") (pinfunction "2_2") (pintype "passive"))
      (node (ref "JP12") (pin "2") (pinfunction "2_2") (pintype "passive"))
      (node (ref "JP13") (pin "2") (pinfunction "2_2") (pintype "passive"))
      (node (ref "JP16") (pin "10") (pinfunction "10_10") (pintype "passive"))
      (node (ref "JP17") (pin "6") (pinfunction "6_6") (pintype "passive"))
      (node (ref "JP5") (pin "2") (pinfunction "2_2") (pintype "passive"))
      (node (ref "JP9") (pin "2") (pinfunction "2_2") (pintype "passive"))
      (node (ref "M1") (pin "3") (pinfunction "S_3") (pintype "passive"))
      (node (ref "M2") (pin "3") (pinfunction "S_3") (pintype "passive"))
      (node (ref "M3") (pin "3") (pinfunction "S_3") (pintype "passive"))
      (node (ref "Q1") (pin "2") (pinfunction "2_2") (pintype "passive"))
      (node (ref "R10") (pin "2") (pinfunction "2_2") (pintype "passive"))
      (node (ref "R11") (pin "2") (pinfunction "2_2") (pintype "passive"))
      (node (ref "R12") (pin "2") (pinfunction "2_2") (pintype "passive"))
      (node (ref "R13") (pin "2") (pinfunction "2_2") (pintype "passive"))
      (node (ref "R14") (pin "2") (pinfunction "2_2") (pintype "passive"))
      (node (ref "R18") (pin "2") (pinfunction "2_2") (pintype "passive"))
      (node (ref "R19") (pin "2") (pinfunction "2_2") (pintype "passive"))
      (node (ref "R20") (pin "2") (pinfunction "2_2") (pintype "passive"))
      (node (ref "R22") (pin "2") (pinfunction "2_2") (pintype "passive"))
      (node (ref "R23") (pin "2") (pinfunction "2_2") (pintype "passive"))
      (node (ref "R24") (pin "2") (pinfunction "2_2") (pintype "passive"))
      (node (ref "R25") (pin "2") (pinfunction "2_2") (pintype "passive"))
      (node (ref "R27") (pin "1") (pinfunction "A_1") (pintype "passive"))
      (node (ref "R28") (pin "2") (pinfunction "2_2") (pintype "passive"))
      (node (ref "R29") (pin "2") (pinfunction "2_2") (pintype "passive"))
      (node (ref "R30") (pin "2") (pinfunction "2_2") (pintype "passive"))
      (node (ref "R6") (pin "1") (pinfunction "A_1") (pintype "passive"))
      (node (ref "R7") (pin "2") (pinfunction "2_2") (pintype "passive"))
      (node (ref "R8") (pin "1") (pinfunction "A_1") (pintype "passive"))
      (node (ref "R9") (pin "1") (pinfunction "A_1") (pintype "passive"))
      (node (ref "U1") (pin "13") (pinfunction "GND1_13") (pintype "power_in"))
      (node (ref "U1") (pin "24") (pinfunction "GND2_24") (pintype "power_in"))
      (node (ref "U1") (pin "PAD") (pinfunction "PAD_PAD") (pintype "power_in"))
      (node (ref "U2") (pin "13") (pinfunction "GND1_13") (pintype "power_in"))
      (node (ref "U2") (pin "24") (pinfunction "GND2_24") (pintype "power_in"))
      (node (ref "U2") (pin "PAD") (pinfunction "PAD_PAD") (pintype "power_in"))
      (node (ref "U3") (pin "13") (pinfunction "GND1_13") (pintype "power_in"))
      (node (ref "U3") (pin "24") (pinfunction "GND2_24") (pintype "power_in"))
      (node (ref "U3") (pin "PAD") (pinfunction "PAD_PAD") (pintype "power_in"))
      (node (ref "U4") (pin "13") (pinfunction "GND1_13") (pintype "power_in"))
      (node (ref "U4") (pin "24") (pinfunction "GND2_24") (pintype "power_in"))
      (node (ref "U4") (pin "PAD") (pinfunction "PAD_PAD") (pintype "power_in"))
      (node (ref "X1") (pin "6") (pinfunction "VSS_6") (pintype "power_in"))
      (node (ref "X1") (pin "MT1") (pinfunction "GND_MT1") (pintype "power_in"))
      (node (ref "X1") (pin "MT2") (pinfunction "GND1_MT2") (pintype "power_in"))
      (node (ref "X2") (pin "5") (pinfunction "5_5") (pintype "input"))
    )
    (net (code "39") (name "Net-(C32-Pad2)") (class "Default")
      (node (ref "C32") (pin "2") (pinfunction "2_2") (pintype "passive"))
      (node (ref "JP14") (pin "2") (pinfunction "2_2") (pintype "passive"))
    )
    (net (code "40") (name "Net-(IC5-VI)") (class "Default")
      (node (ref "C24") (pin "+") (pinfunction "+_+") (pintype "passive"))
      (node (ref "C25") (pin "1") (pinfunction "1_1") (pintype "passive"))
      (node (ref "IC5") (pin "1") (pinfunction "VI_1") (pintype "input"))
      (node (ref "JS16") (pin "1") (pinfunction "1_1") (pintype "passive"))
      (node (ref "R33") (pin "1") (pinfunction "1_1") (pintype "passive"))
    )
    (net (code "41") (name "Net-(IC5-VO)") (class "Default")
      (node (ref "C27") (pin "1") (pinfunction "1_1") (pintype "passive"))
      (node (ref "IC5") (pin "2") (pinfunction "VO_2") (pintype "passive"))
      (node (ref "JP15") (pin "3") (pinfunction "3_3") (pintype "passive"))
    )
    (net (code "42") (name "Net-(IC6-XTAL1)") (class "Default")
      (node (ref "IC6") (pin "8") (pinfunction "XTAL1_8") (pintype "bidirectional"))
      (node (ref "Q1") (pin "3") (pinfunction "3_3") (pintype "passive"))
    )
    (net (code "43") (name "Net-(IC6-XTAL2)") (class "Default")
      (node (ref "IC6") (pin "7") (pinfunction "XTAL2_7") (pintype "bidirectional"))
      (node (ref "Q1") (pin "1") (pinfunction "1_1") (pintype "passive"))
    )
    (net (code "44") (name "Net-(IC7A-O)") (class "Default")
      (node (ref "IC7") (pin "2") (pinfunction "O_2") (pintype "output"))
      (node (ref "X1") (pin "3") (pinfunction "DATA_IN_3") (pintype "input"))
    )
    (net (code "45") (name "Net-(IC7B-O)") (class "Default")
      (node (ref "IC7") (pin "4") (pinfunction "O_4") (pintype "output"))
      (node (ref "X1") (pin "5") (pinfunction "SCLK_5") (pintype "input"))
    )
    (net (code "46") (name "Net-(IC7C-O)") (class "Default")
      (node (ref "IC7") (pin "6") (pinfunction "O_6") (pintype "output"))
      (node (ref "X1") (pin "2") (pinfunction "CS_2") (pintype "input"))
    )
    (net (code "47") (name "Net-(L1-PadC)") (class "Default")
      (node (ref "L1") (pin "C") (pinfunction "C_C") (pintype "passive"))
      (node (ref "R25") (pin "1") (pinfunction "1_1") (pintype "passive"))
    )
    (net (code "48") (name "Net-(M1-D)") (class "Default")
      (node (ref "JP6") (pin "2") (pinfunction "2_2") (pintype "passive"))
      (node (ref "JS1") (pin "2") (pinfunction "2_2") (pintype "passive"))
      (node (ref "M1") (pin "4") (pinfunction "D_4") (pintype "passive"))
    )
    (net (code "49") (name "Net-(M2-D)") (class "Default")
      (node (ref "JP7") (pin "2") (pinfunction "2_2") (pintype "passive"))
      (node (ref "JS2") (pin "2") (pinfunction "2_2") (pintype "passive"))
      (node (ref "M2") (pin "4") (pinfunction "D_4") (pintype "passive"))
    )
    (net (code "50") (name "Net-(M3-D)") (class "Default")
      (node (ref "JP8") (pin "2") (pinfunction "2_2") (pintype "passive"))
      (node (ref "JS3") (pin "2") (pinfunction "2_2") (pintype "passive"))
      (node (ref "M3") (pin "4") (pinfunction "D_4") (pintype "passive"))
    )
    (net (code "51") (name "Net-(R6-E)") (class "Default")
      (node (ref "R17") (pin "1") (pinfunction "1_1") (pintype "passive"))
      (node (ref "R6") (pin "2") (pinfunction "E_2") (pintype "passive"))
    )
    (net (code "52") (name "Net-(R6-S)") (class "Default")
      (node (ref "R6") (pin "W") (pinfunction "S_W") (pintype "passive"))
      (node (ref "U1") (pin "12") (pinfunction "REF_12") (pintype "input"))
    )
    (net (code "53") (name "Net-(R8-E)") (class "Default")
      (node (ref "R35") (pin "1") (pinfunction "1_1") (pintype "passive"))
      (node (ref "R8") (pin "2") (pinfunction "E_2") (pintype "passive"))
    )
    (net (code "54") (name "Net-(R8-S)") (class "Default")
      (node (ref "R8") (pin "W") (pinfunction "S_W") (pintype "passive"))
      (node (ref "U3") (pin "12") (pinfunction "REF_12") (pintype "input"))
    )
    (net (code "55") (name "Net-(R9-E)") (class "Default")
      (node (ref "R38") (pin "1") (pinfunction "1_1") (pintype "passive"))
      (node (ref "R9") (pin "2") (pinfunction "E_2") (pintype "passive"))
    )
    (net (code "56") (name "Net-(R9-S)") (class "Default")
      (node (ref "R9") (pin "W") (pinfunction "S_W") (pintype "passive"))
      (node (ref "U4") (pin "12") (pinfunction "REF_12") (pintype "input"))
    )
    (net (code "57") (name "Net-(R27-E)") (class "Default")
      (node (ref "R27") (pin "2") (pinfunction "E_2") (pintype "passive"))
      (node (ref "R39") (pin "1") (pinfunction "1_1") (pintype "passive"))
    )
    (net (code "58") (name "Net-(R27-S)") (class "Default")
      (node (ref "R27") (pin "W") (pinfunction "S_W") (pintype "passive"))
      (node (ref "U2") (pin "12") (pinfunction "REF_12") (pintype "input"))
    )
    (net (code "59") (name "Net-(U1-CP1)") (class "Default")
      (node (ref "C1") (pin "2") (pinfunction "2_2") (pintype "passive"))
      (node (ref "U1") (pin "1") (pinfunction "CP1_1") (pintype "passive"))
    )
    (net (code "60") (name "Net-(U1-CP2)") (class "Default")
      (node (ref "C1") (pin "1") (pinfunction "1_1") (pintype "passive"))
      (node (ref "U1") (pin "2") (pinfunction "CP2_2") (pintype "passive"))
    )
    (net (code "61") (name "Net-(U1-MS1)") (class "Default")
      (node (ref "MS-X1") (pin "1") (pinfunction "1_1") (pintype "passive"))
      (node (ref "U1") (pin "5") (pinfunction "MS1_5") (pintype "input"))
    )
    (net (code "62") (name "Net-(U1-MS2)") (class "Default")
      (node (ref "MS-X1") (pin "3") (pinfunction "3_3") (pintype "passive"))
      (node (ref "U1") (pin "6") (pinfunction "MS2_6") (pintype "input"))
    )
    (net (code "63") (name "Net-(U1-OUT1A)") (class "Default")
      (node (ref "JP2") (pin "3") (pinfunction "3_3") (pintype "passive"))
      (node (ref "U1") (pin "18") (pinfunction "OUT1A_18") (pintype "output"))
    )
    (net (code "64") (name "Net-(U1-OUT1B)") (class "Default")
      (node (ref "JP2") (pin "4") (pinfunction "4_4") (pintype "passive"))
      (node (ref "U1") (pin "15") (pinfunction "OUT1B_15") (pintype "output"))
    )
    (net (code "65") (name "Net-(U1-OUT2A)") (class "Default")
      (node (ref "JP2") (pin "2") (pinfunction "2_2") (pintype "passive"))
      (node (ref "U1") (pin "19") (pinfunction "OUT2A_19") (pintype "output"))
    )
    (net (code "66") (name "Net-(U1-OUT2B)") (class "Default")
      (node (ref "JP2") (pin "1") (pinfunction "1_1") (pintype "passive"))
      (node (ref "U1") (pin "22") (pinfunction "OUT2B_22") (pintype "output"))
    )
    (net (code "67") (name "Net-(U1-ROSC)") (class "Default")
      (node (ref "R14") (pin "1") (pinfunction "1_1") (pintype "passive"))
      (node (ref "U1") (pin "8") (pinfunction "ROSC_8") (pintype "passive"))
    )
    (net (code "68") (name "Net-(U1-SENSE1)") (class "Default")
      (node (ref "R7") (pin "1") (pinfunction "1_1") (pintype "passive"))
      (node (ref "U1") (pin "17") (pinfunction "SENSE1_17") (pintype "passive"))
    )
    (net (code "69") (name "Net-(U1-SENSE2)") (class "Default")
      (node (ref "R13") (pin "1") (pinfunction "1_1") (pintype "passive"))
      (node (ref "U1") (pin "20") (pinfunction "SENSE2_20") (pintype "passive"))
    )
    (net (code "70") (name "Net-(U1-VCP)") (class "Default")
      (node (ref "C11") (pin "2") (pinfunction "2_2") (pintype "passive"))
      (node (ref "U1") (pin "3") (pinfunction "VCP_3") (pintype "passive"))
    )
    (net (code "71") (name "Net-(U1-VREG)") (class "Default")
      (node (ref "C2") (pin "2") (pinfunction "2_2") (pintype "passive"))
      (node (ref "U1") (pin "4") (pinfunction "VREG_4") (pintype "passive"))
    )
    (net (code "72") (name "Net-(U1-~{RESET})") (class "Default")
      (node (ref "R16") (pin "2") (pinfunction "2_2") (pintype "passive"))
      (node (ref "U1") (pin "7") (pinfunction "~{RESET}_7") (pintype "input"))
      (node (ref "U1") (pin "9") (pinfunction "~{SLEEP}_9") (pintype "input"))
    )
    (net (code "73") (name "Net-(U2-CP1)") (class "Default")
      (node (ref "C46") (pin "2") (pinfunction "2_2") (pintype "passive"))
      (node (ref "U2") (pin "1") (pinfunction "CP1_1") (pintype "passive"))
    )
    (net (code "74") (name "Net-(U2-CP2)") (class "Default")
      (node (ref "C46") (pin "1") (pinfunction "1_1") (pintype "passive"))
      (node (ref "U2") (pin "2") (pinfunction "CP2_2") (pintype "passive"))
    )
    (net (code "75") (name "Net-(U2-MS1)") (class "Default")
      (node (ref "MS-X") (pin "1") (pinfunction "1_1") (pintype "passive"))
      (node (ref "U2") (pin "5") (pinfunction "MS1_5") (pintype "input"))
    )
    (net (code "76") (name "Net-(U2-MS2)") (class "Default")
      (node (ref "MS-X") (pin "3") (pinfunction "3_3") (pintype "passive"))
      (node (ref "U2") (pin "6") (pinfunction "MS2_6") (pintype "input"))
    )
    (net (code "77") (name "Net-(U2-OUT1A)") (class "Default")
      (node (ref "JP1") (pin "3") (pinfunction "3_3") (pintype "passive"))
      (node (ref "U2") (pin "18") (pinfunction "OUT1A_18") (pintype "output"))
    )
    (net (code "78") (name "Net-(U2-OUT1B)") (class "Default")
      (node (ref "JP1") (pin "4") (pinfunction "4_4") (pintype "passive"))
      (node (ref "U2") (pin "15") (pinfunction "OUT1B_15") (pintype "output"))
    )
    (net (code "79") (name "Net-(U2-OUT2A)") (class "Default")
      (node (ref "JP1") (pin "2") (pinfunction "2_2") (pintype "passive"))
      (node (ref "U2") (pin "19") (pinfunction "OUT2A_19") (pintype "output"))
    )
    (net (code "80") (name "Net-(U2-OUT2B)") (class "Default")
      (node (ref "JP1") (pin "1") (pinfunction "1_1") (pintype "passive"))
      (node (ref "U2") (pin "22") (pinfunction "OUT2B_22") (pintype "output"))
    )
    (net (code "81") (name "Net-(U2-ROSC)") (class "Default")
      (node (ref "R30") (pin "1") (pinfunction "1_1") (pintype "passive"))
      (node (ref "U2") (pin "8") (pinfunction "ROSC_8") (pintype "passive"))
    )
    (net (code "82") (name "Net-(U2-SENSE1)") (class "Default")
      (node (ref "R28") (pin "1") (pinfunction "1_1") (pintype "passive"))
      (node (ref "U2") (pin "17") (pinfunction "SENSE1_17") (pintype "passive"))
    )
    (net (code "83") (name "Net-(U2-SENSE2)") (class "Default")
      (node (ref "R29") (pin "1") (pinfunction "1_1") (pintype "passive"))
      (node (ref "U2") (pin "20") (pinfunction "SENSE2_20") (pintype "passive"))
    )
    (net (code "84") (name "Net-(U2-VCP)") (class "Default")
      (node (ref "C49") (pin "2") (pinfunction "2_2") (pintype "passive"))
      (node (ref "U2") (pin "3") (pinfunction "VCP_3") (pintype "passive"))
    )
    (net (code "85") (name "Net-(U2-VREG)") (class "Default")
      (node (ref "C47") (pin "2") (pinfunction "2_2") (pintype "passive"))
      (node (ref "U2") (pin "4") (pinfunction "VREG_4") (pintype "passive"))
    )
    (net (code "86") (name "Net-(U2-~{RESET})") (class "Default")
      (node (ref "R32") (pin "2") (pinfunction "2_2") (pintype "passive"))
      (node (ref "U2") (pin "7") (pinfunction "~{RESET}_7") (pintype "input"))
      (node (ref "U2") (pin "9") (pinfunction "~{SLEEP}_9") (pintype "input"))
    )
    (net (code "87") (name "Net-(U3-CP1)") (class "Default")
      (node (ref "C3") (pin "2") (pinfunction "2_2") (pintype "passive"))
      (node (ref "U3") (pin "1") (pinfunction "CP1_1") (pintype "passive"))
    )
    (net (code "88") (name "Net-(U3-CP2)") (class "Default")
      (node (ref "C3") (pin "1") (pinfunction "1_1") (pintype "passive"))
      (node (ref "U3") (pin "2") (pinfunction "CP2_2") (pintype "passive"))
    )
    (net (code "89") (name "Net-(U3-MS1)") (class "Default")
      (node (ref "MS-X2") (pin "1") (pinfunction "1_1") (pintype "passive"))
      (node (ref "U3") (pin "5") (pinfunction "MS1_5") (pintype "input"))
    )
    (net (code "90") (name "Net-(U3-MS2)") (class "Default")
      (node (ref "MS-X2") (pin "3") (pinfunction "3_3") (pintype "passive"))
      (node (ref "U3") (pin "6") (pinfunction "MS2_6") (pintype "input"))
    )
    (net (code "91") (name "Net-(U3-OUT1A)") (class "Default")
      (node (ref "JP3") (pin "3") (pinfunction "3_3") (pintype "passive"))
      (node (ref "U3") (pin "18") (pinfunction "OUT1A_18") (pintype "output"))
    )
    (net (code "92") (name "Net-(U3-OUT1B)") (class "Default")
      (node (ref "JP3") (pin "4") (pinfunction "4_4") (pintype "passive"))
      (node (ref "U3") (pin "15") (pinfunction "OUT1B_15") (pintype "output"))
    )
    (net (code "93") (name "Net-(U3-OUT2A)") (class "Default")
      (node (ref "JP3") (pin "2") (pinfunction "2_2") (pintype "passive"))
      (node (ref "U3") (pin "19") (pinfunction "OUT2A_19") (pintype "output"))
    )
    (net (code "94") (name "Net-(U3-OUT2B)") (class "Default")
      (node (ref "JP3") (pin "1") (pinfunction "1_1") (pintype "passive"))
      (node (ref "U3") (pin "22") (pinfunction "OUT2B_22") (pintype "output"))
    )
    (net (code "95") (name "Net-(U3-ROSC)") (class "Default")
      (node (ref "R20") (pin "1") (pinfunction "1_1") (pintype "passive"))
      (node (ref "U3") (pin "8") (pinfunction "ROSC_8") (pintype "passive"))
    )
    (net (code "96") (name "Net-(U3-SENSE1)") (class "Default")
      (node (ref "R18") (pin "1") (pinfunction "1_1") (pintype "passive"))
      (node (ref "U3") (pin "17") (pinfunction "SENSE1_17") (pintype "passive"))
    )
    (net (code "97") (name "Net-(U3-SENSE2)") (class "Default")
      (node (ref "R19") (pin "1") (pinfunction "1_1") (pintype "passive"))
      (node (ref "U3") (pin "20") (pinfunction "SENSE2_20") (pintype "passive"))
    )
    (net (code "98") (name "Net-(U3-VCP)") (class "Default")
      (node (ref "C16") (pin "2") (pinfunction "2_2") (pintype "passive"))
      (node (ref "U3") (pin "3") (pinfunction "VCP_3") (pintype "passive"))
    )
    (net (code "99") (name "Net-(U3-VREG)") (class "Default")
      (node (ref "C14") (pin "2") (pinfunction "2_2") (pintype "passive"))
      (node (ref "U3") (pin "4") (pinfunction "VREG_4") (pintype "passive"))
    )
    (net (code "100") (name "Net-(U3-~{RESET})") (class "Default")
      (node (ref "R34") (pin "2") (pinfunction "2_2") (pintype "passive"))
      (node (ref "U3") (pin "7") (pinfunction "~{RESET}_7") (pintype "input"))
      (node (ref "U3") (pin "9") (pinfunction "~{SLEEP}_9") (pintype "input"))
    )
    (net (code "101") (name "Net-(U4-CP1)") (class "Default")
      (node (ref "C4") (pin "2") (pinfunction "2_2") (pintype "passive"))
      (node (ref "U4") (pin "1") (pinfunction "CP1_1") (pintype "passive"))
    )
    (net (code "102") (name "Net-(U4-CP2)") (class "Default")
      (node (ref "C4") (pin "1") (pinfunction "1_1") (pintype "passive"))
      (node (ref "U4") (pin "2") (pinfunction "CP2_2") (pintype "passive"))
    )
    (net (code "103") (name "Net-(U4-MS1)") (class "Default")
      (node (ref "MS-X3") (pin "1") (pinfunction "1_1") (pintype "passive"))
      (node (ref "U4") (pin "5") (pinfunction "MS1_5") (pintype "input"))
    )
    (net (code "104") (name "Net-(U4-MS2)") (class "Default")
      (node (ref "MS-X3") (pin "3") (pinfunction "3_3") (pintype "passive"))
      (node (ref "U4") (pin "6") (pinfunction "MS2_6") (pintype "input"))
    )
    (net (code "105") (name "Net-(U4-OUT1A)") (class "Default")
      (node (ref "JP4") (pin "3") (pinfunction "3_3") (pintype "passive"))
      (node (ref "U4") (pin "18") (pinfunction "OUT1A_18") (pintype "output"))
    )
    (net (code "106") (name "Net-(U4-OUT1B)") (class "Default")
      (node (ref "JP4") (pin "4") (pinfunction "4_4") (pintype "passive"))
      (node (ref "U4") (pin "15") (pinfunction "OUT1B_15") (pintype "output"))
    )
    (net (code "107") (name "Net-(U4-OUT2A)") (class "Default")
      (node (ref "JP4") (pin "2") (pinfunction "2_2") (pintype "passive"))
      (node (ref "U4") (pin "19") (pinfunction "OUT2A_19") (pintype "output"))
    )
    (net (code "108") (name "Net-(U4-OUT2B)") (class "Default")
      (node (ref "JP4") (pin "1") (pinfunction "1_1") (pintype "passive"))
      (node (ref "U4") (pin "22") (pinfunction "OUT2B_22") (pintype "output"))
    )
    (net (code "109") (name "Net-(U4-ROSC)") (class "Default")
      (node (ref "R24") (pin "1") (pinfunction "1_1") (pintype "passive"))
      (node (ref "U4") (pin "8") (pinfunction "ROSC_8") (pintype "passive"))
    )
    (net (code "110") (name "Net-(U4-SENSE1)") (class "Default")
      (node (ref "R22") (pin "1") (pinfunction "1_1") (pintype "passive"))
      (node (ref "U4") (pin "17") (pinfunction "SENSE1_17") (pintype "passive"))
    )
    (net (code "111") (name "Net-(U4-SENSE2)") (class "Default")
      (node (ref "R23") (pin "1") (pinfunction "1_1") (pintype "passive"))
      (node (ref "U4") (pin "20") (pinfunction "SENSE2_20") (pintype "passive"))
    )
    (net (code "112") (name "Net-(U4-VCP)") (class "Default")
      (node (ref "C21") (pin "2") (pinfunction "2_2") (pintype "passive"))
      (node (ref "U4") (pin "3") (pinfunction "VCP_3") (pintype "passive"))
    )
    (net (code "113") (name "Net-(U4-VREG)") (class "Default")
      (node (ref "C19") (pin "2") (pinfunction "2_2") (pintype "passive"))
      (node (ref "U4") (pin "4") (pinfunction "VREG_4") (pintype "passive"))
    )
    (net (code "114") (name "Net-(U4-~{RESET})") (class "Default")
      (node (ref "R37") (pin "2") (pinfunction "2_2") (pintype "passive"))
      (node (ref "U4") (pin "7") (pinfunction "~{RESET}_7") (pintype "input"))
      (node (ref "U4") (pin "9") (pinfunction "~{SLEEP}_9") (pintype "input"))
    )
    (net (code "115") (name "VCC") (class "Default")
      (node (ref "C10") (pin "2") (pinfunction "2_2") (pintype "passive"))
      (node (ref "C15") (pin "2") (pinfunction "2_2") (pintype "passive"))
      (node (ref "C20") (pin "2") (pinfunction "2_2") (pintype "passive"))
      (node (ref "C41") (pin "1") (pinfunction "1_1") (pintype "passive"))
      (node (ref "C42") (pin "1") (pinfunction "1_1") (pintype "passive"))
      (node (ref "C43") (pin "2") (pinfunction "2_2") (pintype "passive"))
      (node (ref "C44") (pin "1") (pinfunction "1_1") (pintype "passive"))
      (node (ref "C45") (pin "2") (pinfunction "2_2") (pintype "passive"))
      (node (ref "C48") (pin "2") (pinfunction "2_2") (pintype "passive"))
      (node (ref "IC6") (pin "17") (pinfunction "VCC_17") (pintype "power_in"))
      (node (ref "IC6") (pin "27") (pinfunction "AVCC_27") (pintype "power_in"))
      (node (ref "IC6") (pin "29") (pinfunction "AREF_29") (pintype "passive"))
      (node (ref "IC6") (pin "38") (pinfunction "VCC_38") (pintype "power_in"))
      (node (ref "IC6") (pin "5") (pinfunction "VCC_5") (pintype "power_in"))
      (node (ref "IC8") (pin "20") (pinfunction "VCC_20") (pintype "power_in"))
      (node (ref "IC8") (pin "4") (pinfunction "VCCIO_4") (pintype "power_in"))
      (node (ref "JP15") (pin "2") (pinfunction "2_2") (pintype "passive"))
      (node (ref "JP16") (pin "9") (pinfunction "9_9") (pintype "passive"))
      (node (ref "JP17") (pin "2") (pinfunction "2_2") (pintype "passive"))
      (node (ref "MS-X") (pin "2") (pinfunction "2_2") (pintype "passive"))
      (node (ref "MS-X1") (pin "2") (pinfunction "2_2") (pintype "passive"))
      (node (ref "MS-X2") (pin "2") (pinfunction "2_2") (pintype "passive"))
      (node (ref "MS-X3") (pin "2") (pinfunction "2_2") (pintype "passive"))
      (node (ref "R1") (pin "1") (pinfunction "1_1") (pintype "passive"))
      (node (ref "R15") (pin "1") (pinfunction "1_1") (pintype "passive"))
      (node (ref "R16") (pin "1") (pinfunction "1_1") (pintype "passive"))
      (node (ref "R17") (pin "2") (pinfunction "2_2") (pintype "passive"))
      (node (ref "R2") (pin "1") (pinfunction "1_1") (pintype "passive"))
      (node (ref "R21") (pin "1") (pinfunction "1_1") (pintype "passive"))
      (node (ref "R26") (pin "2") (pinfunction "2_2") (pintype "passive"))
      (node (ref "R3") (pin "1") (pinfunction "1_1") (pintype "passive"))
      (node (ref "R31") (pin "1") (pinfunction "1_1") (pintype "passive"))
      (node (ref "R32") (pin "1") (pinfunction "1_1") (pintype "passive"))
      (node (ref "R34") (pin "1") (pinfunction "1_1") (pintype "passive"))
      (node (ref "R35") (pin "2") (pinfunction "2_2") (pintype "passive"))
      (node (ref "R36") (pin "1") (pinfunction "1_1") (pintype "passive"))
      (node (ref "R37") (pin "1") (pinfunction "1_1") (pintype "passive"))
      (node (ref "R38") (pin "2") (pinfunction "2_2") (pintype "passive"))
      (node (ref "R39") (pin "2") (pinfunction "2_2") (pintype "passive"))
      (node (ref "R4") (pin "1") (pinfunction "1_1") (pintype "passive"))
      (node (ref "R5") (pin "1") (pinfunction "1_1") (pintype "passive"))
      (node (ref "U1") (pin "10") (pinfunction "VDD_10") (pintype "power_in"))
      (node (ref "U2") (pin "10") (pinfunction "VDD_10") (pintype "power_in"))
      (node (ref "U3") (pin "10") (pinfunction "VDD_10") (pintype "power_in"))
      (node (ref "U4") (pin "10") (pinfunction "VDD_10") (pintype "power_in"))
    )
    (net (code "116") (name "VDD") (class "Default")
      (node (ref "C31") (pin "2") (pinfunction "2_2") (pintype "passive"))
      (node (ref "IC7") (pin "1") (pinfunction "VDD_1") (pintype "power_in"))
      (node (ref "IC8") (pin "17") (pinfunction "3V3OUT_17") (pintype "output"))
      (node (ref "X1") (pin "4") (pinfunction "VDD_4") (pintype "power_in"))
    )
    (net (code "117") (name "VMOT") (class "Default")
      (node (ref "C11") (pin "1") (pinfunction "1_1") (pintype "passive"))
      (node (ref "C12") (pin "+") (pinfunction "+_+") (pintype "passive"))
      (node (ref "C13") (pin "1") (pinfunction "1_1") (pintype "passive"))
      (node (ref "C16") (pin "1") (pinfunction "1_1") (pintype "passive"))
      (node (ref "C17") (pin "+") (pinfunction "+_+") (pintype "passive"))
      (node (ref "C18") (pin "1") (pinfunction "1_1") (pintype "passive"))
      (node (ref "C21") (pin "1") (pinfunction "1_1") (pintype "passive"))
      (node (ref "C22") (pin "+") (pinfunction "+_+") (pintype "passive"))
      (node (ref "C23") (pin "1") (pinfunction "1_1") (pintype "passive"))
      (node (ref "C28") (pin "+") (pinfunction "+_+") (pintype "passive"))
      (node (ref "C29") (pin "+") (pinfunction "+_+") (pintype "passive"))
      (node (ref "C30") (pin "+") (pinfunction "+_+") (pintype "passive"))
      (node (ref "C49") (pin "1") (pinfunction "1_1") (pintype "passive"))
      (node (ref "C50") (pin "+") (pinfunction "+_+") (pintype "passive"))
      (node (ref "C51") (pin "1") (pinfunction "1_1") (pintype "passive"))
      (node (ref "JP5") (pin "1") (pinfunction "1_1") (pintype "passive"))
      (node (ref "JP6") (pin "1") (pinfunction "1_1") (pintype "passive"))
      (node (ref "JP7") (pin "1") (pinfunction "1_1") (pintype "passive"))
      (node (ref "JP8") (pin "1") (pinfunction "1_1") (pintype "passive"))
      (node (ref "JS16") (pin "2") (pinfunction "2_2") (pintype "passive"))
      (node (ref "R33") (pin "2") (pinfunction "2_2") (pintype "passive"))
      (node (ref "U1") (pin "16") (pinfunction "VBB1_16") (pintype "power_in"))
      (node (ref "U1") (pin "21") (pinfunction "VBB2_21") (pintype "power_in"))
      (node (ref "U2") (pin "16") (pinfunction "VBB1_16") (pintype "power_in"))
      (node (ref "U2") (pin "21") (pinfunction "VBB2_21") (pintype "power_in"))
      (node (ref "U3") (pin "16") (pinfunction "VBB1_16") (pintype "power_in"))
      (node (ref "U3") (pin "21") (pinfunction "VBB2_21") (pintype "power_in"))
      (node (ref "U4") (pin "16") (pinfunction "VBB1_16") (pintype "power_in"))
      (node (ref "U4") (pin "21") (pinfunction "VBB2_21") (pintype "power_in"))
    )
    (net (code "118") (name "unconnected-(IC8-CTS-Pad11)") (class "Default")
      (node (ref "IC8") (pin "11") (pinfunction "CTS_11") (pintype "bidirectional"))
    )
    (net (code "119") (name "unconnected-(IC8-RTS-Pad3)") (class "Default")
      (node (ref "IC8") (pin "3") (pinfunction "RTS_3") (pintype "bidirectional"))
    )
    (net (code "120") (name "unconnected-(IC8-RXLED-Pad22)") (class "Default")
      (node (ref "IC8") (pin "22") (pinfunction "RXLED_22") (pintype "bidirectional"))
    )
    (net (code "121") (name "unconnected-(IC8-TXLED-Pad23)") (class "Default")
      (node (ref "IC8") (pin "23") (pinfunction "TXLED_23") (pintype "bidirectional"))
    )
    (net (code "122") (name "unconnected-(X1-CARD_DETECT-PadCD1)") (class "Default")
      (node (ref "X1") (pin "CD1") (pinfunction "CARD_DETECT_CD1") (pintype "passive"))
    )
    (net (code "123") (name "unconnected-(X1-CARD_DETECT1-PadCD2)") (class "Default")
      (node (ref "X1") (pin "CD2") (pinfunction "CARD_DETECT1_CD2") (pintype "passive"))
    )
    (net (code "124") (name "unconnected-(X1-DAT1-Pad8)") (class "Default")
      (node (ref "X1") (pin "8") (pinfunction "DAT1_8") (pintype "bidirectional"))
    )
    (net (code "125") (name "unconnected-(X1-DAT2-Pad1)") (class "Default")
      (node (ref "X1") (pin "1") (pinfunction "DAT2_1") (pintype "bidirectional"))
    )
    (net (code "126") (name "unconnected-(X2-Pad4)") (class "Default")
      (node (ref "X2") (pin "4") (pinfunction "4_4") (pintype "input"))
    )
  )
)
